# Sheet1.net
KiCad netlist of a schematic drawn in Altium Designer
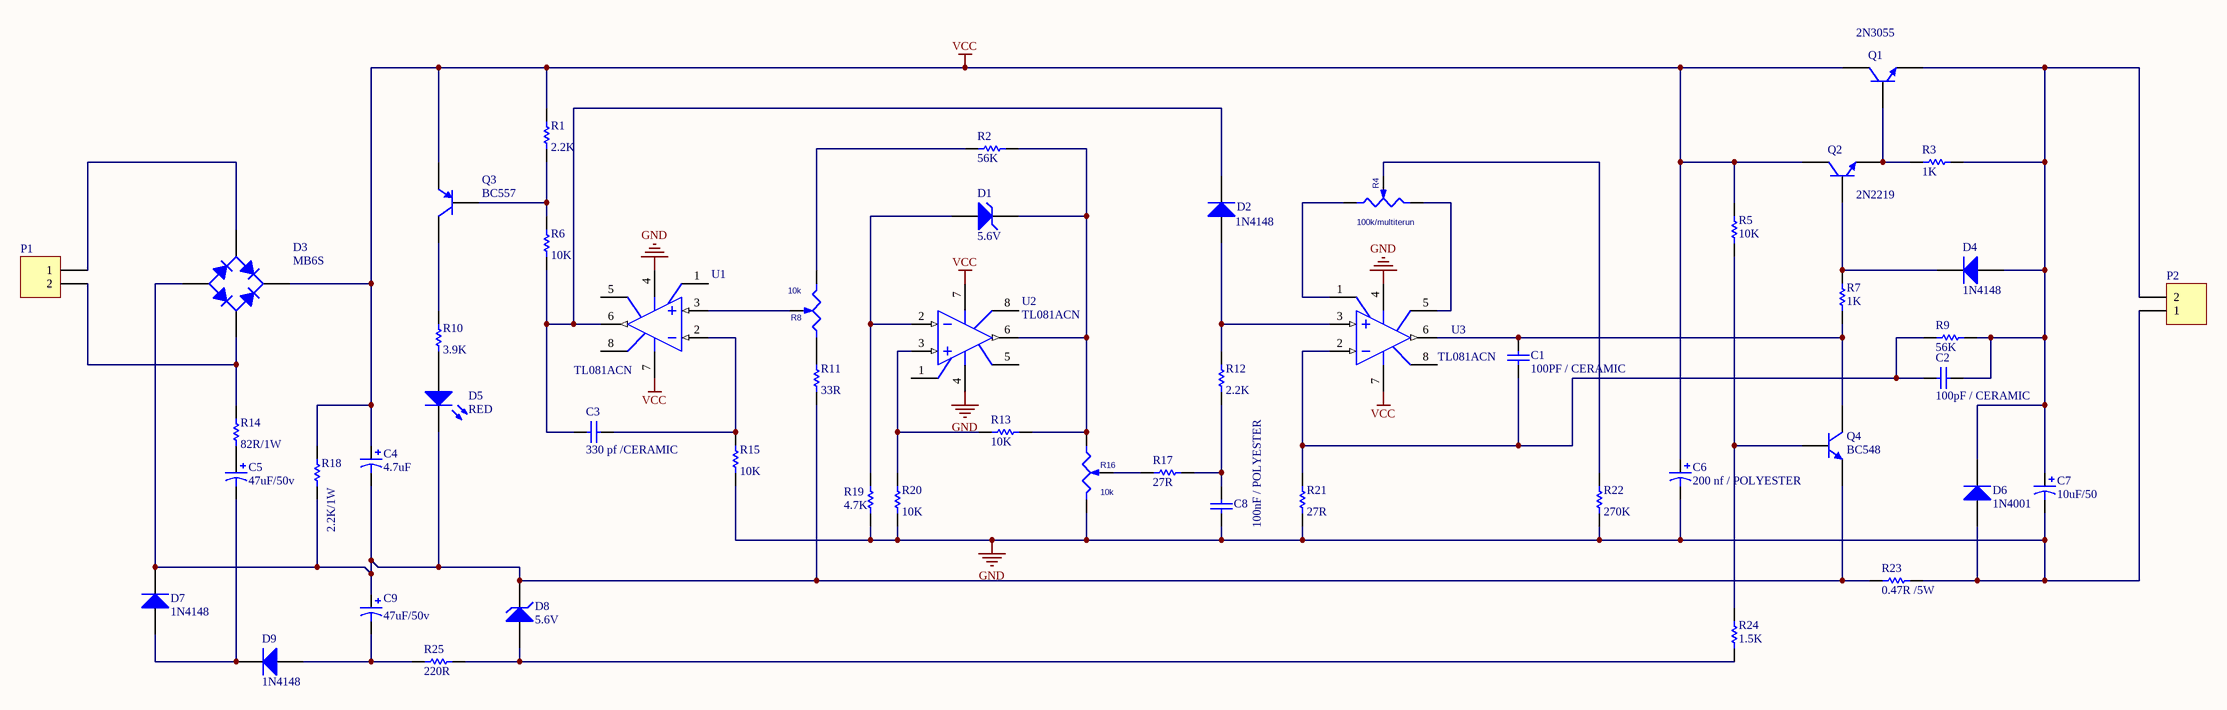
[diagram p0: Sheet1.SchDoc]

(export (version "E")
  (design (tool "Eeschema 10.0.6"))
  (components
    (comp (ref "C1")
      (value "100PF / CERAMIC")
      (footprint "RAD-0.1_cap")
      (description "Capacitor")
      (fields (field (name "PUBLISHER") "Altium Limited"))
      (libsource (lib "Miscellaneous Devices") (part "Cap"))
    )
    (comp (ref "C2")
      (value "100pF / CERAMIC")
      (footprint "RAD-0.1_cap")
      (description "Capacitor")
      (fields (field (name "PUBLISHER") "Altium Limited"))
      (libsource (lib "Miscellaneous Devices") (part "Cap"))
    )
    (comp (ref "C3")
      (value "330 pf /CERAMIC")
      (footprint "RAD-0.1_cap")
      (description "Capacitor")
      (fields (field (name "PUBLISHER") "Altium Limited"))
      (libsource (lib "Miscellaneous Devices") (part "Cap"))
    )
    (comp (ref "C4")
      (value "4.7uF")
      (footprint "Rad.1/.2-SMALL - duplicate")
      (description "Polarized Capacitor (Radial)")
      (fields (field (name "PUBLISHER") "Altium Limited"))
      (libsource (lib "Miscellaneous Devices") (part "Cap Pol1"))
    )
    (comp (ref "C5")
      (value "47uF/50v")
      (footprint "Rad.1/.2-SMALL - duplicate")
      (description "Polarized Capacitor (Radial)")
      (fields (field (name "PUBLISHER") "Altium Limited"))
      (libsource (lib "Miscellaneous Devices") (part "Cap Pol1"))
    )
    (comp (ref "C6")
      (value "200 nf / POLYESTER")
      (footprint "Rad.1/.2-SMALL - duplicate")
      (description "Polarized Capacitor (Radial)")
      (fields (field (name "PUBLISHER") "Altium Limited"))
      (libsource (lib "Miscellaneous Devices") (part "Cap Pol1"))
    )
    (comp (ref "C7")
      (value "10uF/50")
      (footprint "Rad.1/.2-SMALL - duplicate")
      (description "Polarized Capacitor (Radial)")
      (fields (field (name "PUBLISHER") "Altium Limited"))
      (libsource (lib "Miscellaneous Devices") (part "Cap Pol1"))
    )
    (comp (ref "C8")
      (value "100nF / POLYESTER")
      (footprint "RAD-0.2- duplicate")
      (description "Capacitor")
      (fields (field (name "PUBLISHER") "Altium Limited"))
      (libsource (lib "Miscellaneous Devices") (part "Cap"))
    )
    (comp (ref "C9")
      (value "47uF/50v")
      (footprint "Rad.1/.2-SMALL - duplicate")
      (description "Polarized Capacitor (Radial)")
      (fields (field (name "PUBLISHER") "Altium Limited"))
      (libsource (lib "Miscellaneous Devices") (part "Cap Pol1"))
    )
    (comp (ref "D1")
      (value "5.6V")
      (footprint "DIODE_ZENER.AXIAL0.3")
      (description "Zener Diode")
      (fields (field (name "PUBLISHER") "Altium Limited"))
      (libsource (lib "Miscellaneous Devices") (part "D Zener"))
    )
    (comp (ref "D2")
      (value "1N4148")
      (footprint "Dioad_1n400x_2")
      (description "1 Amp General Purpose Rectifier")
      (fields (field (name "PUBLISHER") "Altium Limited"))
      (libsource (lib "Miscellaneous Devices") (part "Diode 1N4007"))
    )
    (comp (ref "D3")
      (value "MB6S")
      (footprint "Bridge")
      (description "Full Wave Diode Bridge")
      (fields (field (name "PUBLISHER") "Altium Limited"))
      (libsource (lib "Miscellaneous Devices") (part "Bridge1"))
    )
    (comp (ref "D4")
      (value "1N4148")
      (footprint "Dioad_1n400x_2")
      (description "1 Amp General Purpose Rectifier")
      (fields (field (name "PUBLISHER") "Altium Limited"))
      (libsource (lib "Miscellaneous Devices") (part "Diode 1N4007"))
    )
    (comp (ref "D5")
      (value "RED")
      (footprint "Led_3mil - RED")
      (description "Typical INFRARED GaAs LED")
      (fields (field (name "PUBLISHER") "Altium Limited"))
      (libsource (lib "Miscellaneous Devices") (part "LED0"))
    )
    (comp (ref "D6")
      (value "1N4001")
      (footprint "Dioad_1n400x_2")
      (description "1 Amp General Purpose Rectifier")
      (fields (field (name "PUBLISHER") "Altium Limited"))
      (libsource (lib "Miscellaneous Devices") (part "Diode 1N4007"))
    )
    (comp (ref "D7")
      (value "1N4148")
      (footprint "Dioad_1n400x_2")
      (description "1 Amp General Purpose Rectifier")
      (fields (field (name "PUBLISHER") "Altium Limited"))
      (libsource (lib "Miscellaneous Devices") (part "Diode 1N4007"))
    )
    (comp (ref "D8")
      (value "5.6V")
      (footprint "DIODE_ZENER.AXIAL0.3")
      (description "Zener Diode")
      (fields (field (name "PUBLISHER") "Altium Limited"))
      (libsource (lib "Miscellaneous Devices") (part "D Zener"))
    )
    (comp (ref "D9")
      (value "1N4148")
      (footprint "Dioad_1n400x_2")
      (description "1 Amp General Purpose Rectifier")
      (fields (field (name "PUBLISHER") "Altium Limited"))
      (libsource (lib "Miscellaneous Devices") (part "Diode 1N4007"))
    )
    (comp (ref "P1")
      (value "24VDC/3A")
      (footprint "Blue Connector 1*2 -kf301")
      (description "Blue Connector 1*2 -kf301")
      (fields (field (name "PUBLISHER") "Altium Limited"))
      (libsource (lib "") (part "Header 2H_1"))
    )
    (comp (ref "P2")
      (value "Blue Connector 1*2 -kf301")
      (footprint "Blue Connector 1*2 -kf301")
      (fields (field (name "PUBLISHER") "Altium Limited"))
      (libsource (lib "Miscellaneous Connectors") (part "Header 2H"))
    )
    (comp (ref "Q1")
      (value "2N3055")
      (footprint "Blue Connector 1*3 -kf301")
      (description "NPN General Purpose Amplifier")
      (fields (field (name "PUBLISHER") "Altium Limited"))
      (libsource (lib "Miscellaneous Devices") (part "2N3904"))
    )
    (comp (ref "Q2")
      (value "2N2219")
      (footprint "TO-92A")
      (description "NPN General Purpose Amplifier")
      (fields (field (name "PUBLISHER") "Altium Limited"))
      (libsource (lib "Miscellaneous Devices") (part "2N3904"))
    )
    (comp (ref "Q3")
      (value "BC557")
      (footprint "TO-92A")
      (description "PNP General Purpose Amplifier")
      (fields (field (name "PUBLISHER") "Altium Limited"))
      (libsource (lib "Miscellaneous Devices") (part "2N3906"))
    )
    (comp (ref "Q4")
      (value "BC548")
      (footprint "TO-92A")
      (description "NPN General Purpose Amplifier")
      (fields (field (name "PUBLISHER") "Altium Limited"))
      (libsource (lib "Miscellaneous Devices") (part "2N3904"))
    )
    (comp (ref "R1")
      (value "2.2K")
      (footprint "AXIAL0.4 - 1k")
      (description "Resistor")
      (fields (field (name "PUBLISHER") "Altium Limited"))
      (libsource (lib "Miscellaneous Devices") (part "Res1"))
    )
    (comp (ref "R2")
      (value "56K")
      (footprint "AXIAL0.4 - 1k")
      (description "Resistor")
      (fields (field (name "PUBLISHER") "Altium Limited"))
      (libsource (lib "Miscellaneous Devices") (part "Res1"))
    )
    (comp (ref "R3")
      (value "1K")
      (footprint "AXIAL0.4 - 1k")
      (description "Resistor")
      (fields (field (name "PUBLISHER") "Altium Limited"))
      (libsource (lib "Miscellaneous Devices") (part "Res1"))
    )
    (comp (ref "R4") (value "100k/multiterun") (footprint "MULTITERN") (libsource (lib "*") (part "POT")))
    (comp (ref "R5")
      (value "10K")
      (footprint "AXIAL0.4 - 1k")
      (description "Resistor")
      (fields (field (name "PUBLISHER") "Altium Limited"))
      (libsource (lib "Miscellaneous Devices") (part "Res1"))
    )
    (comp (ref "R6")
      (value "10K")
      (footprint "AXIAL0.4 - 1k")
      (description "Resistor")
      (fields (field (name "PUBLISHER") "Altium Limited"))
      (libsource (lib "Miscellaneous Devices") (part "Res1"))
    )
    (comp (ref "R7")
      (value "1K")
      (footprint "AXIAL0.4 - 1k")
      (description "Resistor")
      (fields (field (name "PUBLISHER") "Altium Limited"))
      (libsource (lib "Miscellaneous Devices") (part "Res1"))
    )
    (comp (ref "R8") (value "10k") (footprint "Blue Connector 1*3 -kf301") (libsource (lib "*") (part "POT")))
    (comp (ref "R9")
      (value "56K")
      (footprint "AXIAL0.4 - 1k")
      (description "Resistor")
      (fields (field (name "PUBLISHER") "Altium Limited"))
      (libsource (lib "Miscellaneous Devices") (part "Res1"))
    )
    (comp (ref "R10")
      (value "3.9K")
      (footprint "AXIAL0.4 - 1k")
      (description "Resistor")
      (fields (field (name "PUBLISHER") "Altium Limited"))
      (libsource (lib "Miscellaneous Devices") (part "Res1"))
    )
    (comp (ref "R11")
      (value "33R")
      (footprint "AXIAL0.4 - 1k")
      (description "Resistor")
      (fields (field (name "PUBLISHER") "Altium Limited"))
      (libsource (lib "Miscellaneous Devices") (part "Res1"))
    )
    (comp (ref "R12")
      (value "2.2K")
      (footprint "AXIAL0.4 - 1k")
      (description "Resistor")
      (fields (field (name "PUBLISHER") "Altium Limited"))
      (libsource (lib "Miscellaneous Devices") (part "Res1"))
    )
    (comp (ref "R13")
      (value "10K")
      (footprint "AXIAL0.4 - 1k")
      (description "Resistor")
      (fields (field (name "PUBLISHER") "Altium Limited"))
      (libsource (lib "Miscellaneous Devices") (part "Res1"))
    )
    (comp (ref "R14")
      (value "82R/1W")
      (footprint "AXIAL0.4 - 1k")
      (description "Resistor")
      (fields (field (name "PUBLISHER") "Altium Limited"))
      (libsource (lib "Miscellaneous Devices") (part "Res1"))
    )
    (comp (ref "R15")
      (value "10K")
      (footprint "AXIAL0.4 - 1k")
      (description "Resistor")
      (fields (field (name "PUBLISHER") "Altium Limited"))
      (libsource (lib "Miscellaneous Devices") (part "Res1"))
    )
    (comp (ref "R16")
      (value "10k")
      (footprint "Blue Connector 1*3 -kf301")
      (libsource (lib "*") (part "POT"))
    )
    (comp (ref "R17")
      (value "27R")
      (footprint "AXIAL0.4 - 1k")
      (description "Resistor")
      (fields (field (name "PUBLISHER") "Altium Limited"))
      (libsource (lib "Miscellaneous Devices") (part "Res1"))
    )
    (comp (ref "R18")
      (value "2.2K/1W")
      (footprint "AXIAL0.4 - 1k")
      (description "Resistor")
      (fields (field (name "PUBLISHER") "Altium Limited"))
      (libsource (lib "Miscellaneous Devices") (part "Res1"))
    )
    (comp (ref "R19")
      (value "4.7K")
      (footprint "AXIAL0.4 - 1k")
      (description "Resistor")
      (fields (field (name "PUBLISHER") "Altium Limited"))
      (libsource (lib "Miscellaneous Devices") (part "Res1"))
    )
    (comp (ref "R20")
      (value "10K")
      (footprint "AXIAL0.4 - 1k")
      (description "Resistor")
      (fields (field (name "PUBLISHER") "Altium Limited"))
      (libsource (lib "Miscellaneous Devices") (part "Res1"))
    )
    (comp (ref "R21")
      (value "27R")
      (footprint "AXIAL0.4 - 1k")
      (description "Resistor")
      (fields (field (name "PUBLISHER") "Altium Limited"))
      (libsource (lib "Miscellaneous Devices") (part "Res1"))
    )
    (comp (ref "R22")
      (value "270K")
      (footprint "AXIAL0.4 - 1k")
      (description "Resistor")
      (fields (field (name "PUBLISHER") "Altium Limited"))
      (libsource (lib "Miscellaneous Devices") (part "Res1"))
    )
    (comp (ref "R23")
      (value "0.47R /5W")
      (footprint "AXIAL0.4 - 1k")
      (description "Resistor")
      (fields (field (name "PUBLISHER") "Altium Limited"))
      (libsource (lib "Miscellaneous Devices") (part "Res1"))
    )
    (comp (ref "R24")
      (value "1.5K")
      (footprint "AXIAL0.4 - 1k")
      (description "Resistor")
      (fields (field (name "PUBLISHER") "Altium Limited"))
      (libsource (lib "Miscellaneous Devices") (part "Res1"))
    )
    (comp (ref "R25")
      (value "220R")
      (footprint "AXIAL0.4 - 1k")
      (description "Resistor")
      (fields (field (name "PUBLISHER") "Altium Limited"))
      (libsource (lib "Miscellaneous Devices") (part "Res1"))
    )
    (comp (ref "U1")
      (value "TL081ACN")
      (footprint "DIP8")
      (description "General-Purpose J-FET Single Operational Amplifier")
      (fields (field (name "PUBLISHER") "Altium Limited"))
      (libsource (lib "ST Operational Amplifier") (part "TL081ACN"))
    )
    (comp (ref "U2")
      (value "TL081ACN")
      (footprint "DIP8")
      (description "General-Purpose J-FET Single Operational Amplifier")
      (fields (field (name "PUBLISHER") "Altium Limited"))
      (libsource (lib "ST Operational Amplifier") (part "TL081ACN"))
    )
    (comp (ref "U3")
      (value "TL081ACN")
      (footprint "DIP8")
      (description "General-Purpose J-FET Single Operational Amplifier")
      (fields (field (name "PUBLISHER") "Altium Limited"))
      (libsource (lib "ST Operational Amplifier") (part "TL081ACN"))
    )
  )
  (nets
    (net (code "1") (name "GND") (class "Default")
      (node (ref "C6") (pin "2") (pintype "passive"))
      (node (ref "C7") (pin "2") (pintype "passive"))
      (node (ref "C8") (pin "1") (pinfunction "1_1") (pintype "passive"))
      (node (ref "D6") (pin "1") (pinfunction "A_1") (pintype "passive"))
      (node (ref "P2") (pin "1") (pinfunction "1_1") (pintype "passive"))
      (node (ref "R15") (pin "1") (pinfunction "1_1") (pintype "passive"))
      (node (ref "R16") (pin "1") (pinfunction "A_1") (pintype "passive"))
      (node (ref "R19") (pin "2") (pinfunction "2_2") (pintype "passive"))
      (node (ref "R20") (pin "1") (pinfunction "1_1") (pintype "passive"))
      (node (ref "R21") (pin "1") (pinfunction "1_1") (pintype "passive"))
      (node (ref "R22") (pin "1") (pinfunction "1_1") (pintype "passive"))
      (node (ref "R23") (pin "1") (pinfunction "1_1") (pintype "passive"))
      (node (ref "U1") (pin "4") (pinfunction "V-_4") (pintype "power_in"))
      (node (ref "U2") (pin "4") (pinfunction "V-_4") (pintype "power_in"))
      (node (ref "U3") (pin "4") (pinfunction "V-_4") (pintype "power_in"))
    )
    (net (code "2") (name "Net-(C5-Pad1)") (class "Default")
      (node (ref "C5") (pin "1") (pintype "passive"))
      (node (ref "R14") (pin "1") (pinfunction "1_1") (pintype "passive"))
    )
    (net (code "3") (name "Net-(C8-Pad2)") (class "Default")
      (node (ref "C8") (pin "2") (pinfunction "2_2") (pintype "passive"))
      (node (ref "R12") (pin "1") (pinfunction "1_1") (pintype "passive"))
      (node (ref "R17") (pin "1") (pinfunction "1_1") (pintype "passive"))
    )
    (net (code "4") (name "Net-(D2-A)") (class "Default")
      (node (ref "D2") (pin "1") (pinfunction "A_1") (pintype "passive"))
      (node (ref "R12") (pin "2") (pinfunction "2_2") (pintype "passive"))
      (node (ref "U3") (pin "3") (pinfunction "IN+_3") (pintype "input"))
    )
    (net (code "5") (name "Net-(D2-K)") (class "Default")
      (node (ref "C3") (pin "2") (pinfunction "2_2") (pintype "passive"))
      (node (ref "D2") (pin "2") (pinfunction "K_2") (pintype "passive"))
      (node (ref "R6") (pin "1") (pinfunction "1_1") (pintype "passive"))
      (node (ref "U1") (pin "6") (pinfunction "OUT_6") (pintype "output"))
    )
    (net (code "6") (name "Net-(D3-A)") (class "Default")
      (node (ref "C4") (pin "2") (pintype "passive"))
      (node (ref "C9") (pin "1") (pintype "passive"))
      (node (ref "D3") (pin "3") (pinfunction "A_3") (pintype "passive"))
      (node (ref "D5") (pin "2") (pinfunction "K_2") (pintype "passive"))
      (node (ref "D7") (pin "2") (pinfunction "K_2") (pintype "passive"))
      (node (ref "D8") (pin "K") (pinfunction "K_K") (pintype "passive"))
      (node (ref "Q4") (pin "1") (pinfunction "E_1") (pintype "passive"))
      (node (ref "R11") (pin "1") (pinfunction "1_1") (pintype "passive"))
      (node (ref "R18") (pin "1") (pinfunction "1_1") (pintype "passive"))
      (node (ref "R23") (pin "2") (pinfunction "2_2") (pintype "passive"))
    )
    (net (code "7") (name "Net-(D3-C-Pad2)") (class "Default")
      (node (ref "D3") (pin "2") (pinfunction "C_2") (pintype "passive"))
      (node (ref "P1") (pin "2") (pinfunction "2_2") (pintype "passive"))
      (node (ref "R14") (pin "2") (pinfunction "2_2") (pintype "passive"))
    )
    (net (code "8") (name "Net-(D3-C-Pad4)") (class "Default")
      (node (ref "D3") (pin "4") (pinfunction "C_4") (pintype "passive"))
      (node (ref "P1") (pin "1") (pinfunction "1_1") (pintype "passive"))
    )
    (net (code "9") (name "Net-(D4-A)") (class "Default")
      (node (ref "C2") (pin "1") (pinfunction "1_1") (pintype "passive"))
      (node (ref "C7") (pin "1") (pintype "passive"))
      (node (ref "D4") (pin "1") (pinfunction "A_1") (pintype "passive"))
      (node (ref "D6") (pin "2") (pinfunction "K_2") (pintype "passive"))
      (node (ref "P2") (pin "2") (pinfunction "2_2") (pintype "passive"))
      (node (ref "Q1") (pin "1") (pinfunction "E_1") (pintype "passive"))
      (node (ref "R3") (pin "2") (pinfunction "2_2") (pintype "passive"))
      (node (ref "R9") (pin "2") (pinfunction "2_2") (pintype "passive"))
    )
    (net (code "10") (name "Net-(D4-K)") (class "Default")
      (node (ref "D4") (pin "2") (pinfunction "K_2") (pintype "passive"))
      (node (ref "Q2") (pin "2") (pinfunction "B_2") (pintype "passive"))
      (node (ref "R7") (pin "1") (pinfunction "1_1") (pintype "passive"))
    )
    (net (code "11") (name "Net-(D5-A)") (class "Default")
      (node (ref "D5") (pin "1") (pinfunction "A_1") (pintype "passive"))
      (node (ref "R10") (pin "1") (pinfunction "1_1") (pintype "passive"))
    )
    (net (code "12") (name "Net-(D7-A)") (class "Default")
      (node (ref "C5") (pin "2") (pintype "passive"))
      (node (ref "D7") (pin "1") (pinfunction "A_1") (pintype "passive"))
      (node (ref "D9") (pin "2") (pinfunction "K_2") (pintype "passive"))
    )
    (net (code "13") (name "Net-(D8-PadA)") (class "Default")
      (node (ref "D8") (pin "A") (pinfunction "A_A") (pintype "passive"))
      (node (ref "R24") (pin "2") (pinfunction "2_2") (pintype "passive"))
      (node (ref "R25") (pin "1") (pinfunction "1_1") (pintype "passive"))
    )
    (net (code "14") (name "Net-(D9-A)") (class "Default")
      (node (ref "C9") (pin "2") (pintype "passive"))
      (node (ref "D9") (pin "1") (pinfunction "A_1") (pintype "passive"))
      (node (ref "R25") (pin "2") (pinfunction "2_2") (pintype "passive"))
    )
    (net (code "15") (name "Net-(Q1-B)") (class "Default")
      (node (ref "Q1") (pin "2") (pinfunction "B_2") (pintype "passive"))
      (node (ref "Q2") (pin "1") (pinfunction "E_1") (pintype "passive"))
      (node (ref "R3") (pin "1") (pinfunction "1_1") (pintype "passive"))
    )
    (net (code "16") (name "Net-(Q3-B)") (class "Default")
      (node (ref "Q3") (pin "2") (pinfunction "B_2") (pintype "passive"))
      (node (ref "R1") (pin "1") (pinfunction "1_1") (pintype "passive"))
      (node (ref "R6") (pin "2") (pinfunction "2_2") (pintype "passive"))
    )
    (net (code "17") (name "Net-(Q3-C)") (class "Default")
      (node (ref "Q3") (pin "3") (pinfunction "C_3") (pintype "passive"))
      (node (ref "R10") (pin "2") (pinfunction "2_2") (pintype "passive"))
    )
    (net (code "18") (name "Net-(Q4-B)") (class "Default")
      (node (ref "Q4") (pin "2") (pinfunction "B_2") (pintype "passive"))
      (node (ref "R24") (pin "1") (pinfunction "1_1") (pintype "passive"))
      (node (ref "R5") (pin "2") (pinfunction "2_2") (pintype "passive"))
    )
    (net (code "19") (name "Net-(Q4-C)") (class "Default")
      (node (ref "C1") (pin "2") (pinfunction "2_2") (pintype "passive"))
      (node (ref "Q4") (pin "3") (pinfunction "C_3") (pintype "passive"))
      (node (ref "R7") (pin "2") (pinfunction "2_2") (pintype "passive"))
      (node (ref "U3") (pin "6") (pinfunction "OUT_6") (pintype "output"))
    )
    (net (code "20") (name "Net-(R4-A)") (class "Default")
      (node (ref "R4") (pin "1") (pinfunction "A_1") (pintype "passive"))
      (node (ref "U3") (pin "5") (pinfunction "OS_NULL_5") (pintype "passive"))
    )
    (net (code "21") (name "Net-(R4-B)") (class "Default")
      (node (ref "R4") (pin "3") (pinfunction "B_3") (pintype "passive"))
      (node (ref "U3") (pin "1") (pinfunction "OS_NULL_1") (pintype "passive"))
    )
    (net (code "22") (name "Net-(R4-WIPER)") (class "Default")
      (node (ref "R22") (pin "2") (pinfunction "2_2") (pintype "passive"))
      (node (ref "R4") (pin "2") (pinfunction "WIPER_2") (pintype "passive"))
    )
    (net (code "23") (name "Net-(R8-A)") (class "Default")
      (node (ref "R2") (pin "2") (pinfunction "2_2") (pintype "passive"))
      (node (ref "R8") (pin "1") (pinfunction "A_1") (pintype "passive"))
    )
    (net (code "24") (name "Net-(R8-B)") (class "Default")
      (node (ref "R11") (pin "2") (pinfunction "2_2") (pintype "passive"))
      (node (ref "R8") (pin "3") (pinfunction "B_3") (pintype "passive"))
    )
    (net (code "25") (name "Net-(R8-WIPER)") (class "Default")
      (node (ref "R8") (pin "2") (pinfunction "WIPER_2") (pintype "passive"))
      (node (ref "U1") (pin "3") (pinfunction "IN+_3") (pintype "input"))
    )
    (net (code "26") (name "Net-(R16-B)") (class "Default")
      (node (ref "D1") (pin "K") (pinfunction "K_K") (pintype "passive"))
      (node (ref "R13") (pin "1") (pinfunction "1_1") (pintype "passive"))
      (node (ref "R16") (pin "3") (pinfunction "B_3") (pintype "passive"))
      (node (ref "R2") (pin "1") (pinfunction "1_1") (pintype "passive"))
      (node (ref "U2") (pin "6") (pinfunction "OUT_6") (pintype "output"))
    )
    (net (code "27") (name "Net-(R16-WIPER)") (class "Default")
      (node (ref "R16") (pin "2") (pinfunction "WIPER_2") (pintype "passive"))
      (node (ref "R17") (pin "2") (pinfunction "2_2") (pintype "passive"))
    )
    (net (code "28") (name "Net-(U1-IN-)") (class "Default")
      (node (ref "C3") (pin "1") (pinfunction "1_1") (pintype "passive"))
      (node (ref "R15") (pin "2") (pinfunction "2_2") (pintype "passive"))
      (node (ref "U1") (pin "2") (pinfunction "IN-_2") (pintype "input"))
    )
    (net (code "29") (name "Net-(U2-IN+)") (class "Default")
      (node (ref "R13") (pin "2") (pinfunction "2_2") (pintype "passive"))
      (node (ref "R20") (pin "2") (pinfunction "2_2") (pintype "passive"))
      (node (ref "U2") (pin "3") (pinfunction "IN+_3") (pintype "input"))
    )
    (net (code "30") (name "Net-(U2-IN-)") (class "Default")
      (node (ref "D1") (pin "A") (pinfunction "A_A") (pintype "passive"))
      (node (ref "R19") (pin "1") (pinfunction "1_1") (pintype "passive"))
      (node (ref "U2") (pin "2") (pinfunction "IN-_2") (pintype "input"))
    )
    (net (code "31") (name "Net-(U3-IN-)") (class "Default")
      (node (ref "C1") (pin "1") (pinfunction "1_1") (pintype "passive"))
      (node (ref "C2") (pin "2") (pinfunction "2_2") (pintype "passive"))
      (node (ref "R21") (pin "2") (pinfunction "2_2") (pintype "passive"))
      (node (ref "R9") (pin "1") (pinfunction "1_1") (pintype "passive"))
      (node (ref "U3") (pin "2") (pinfunction "IN-_2") (pintype "input"))
    )
    (net (code "32") (name "VCC") (class "Default")
      (node (ref "C4") (pin "1") (pintype "passive"))
      (node (ref "C6") (pin "1") (pintype "passive"))
      (node (ref "D3") (pin "1") (pinfunction "K_1") (pintype "passive"))
      (node (ref "Q1") (pin "3") (pinfunction "C_3") (pintype "passive"))
      (node (ref "Q2") (pin "3") (pinfunction "C_3") (pintype "passive"))
      (node (ref "Q3") (pin "1") (pinfunction "E_1") (pintype "passive"))
      (node (ref "R1") (pin "2") (pinfunction "2_2") (pintype "passive"))
      (node (ref "R18") (pin "2") (pinfunction "2_2") (pintype "passive"))
      (node (ref "R5") (pin "1") (pinfunction "1_1") (pintype "passive"))
      (node (ref "U1") (pin "7") (pinfunction "V+_7") (pintype "power_in"))
      (node (ref "U2") (pin "7") (pinfunction "V+_7") (pintype "power_in"))
      (node (ref "U3") (pin "7") (pinfunction "V+_7") (pintype "power_in"))
    )
    (net (code "33") (name "unconnected-(U1-NC-Pad8)") (class "Default")
      (node (ref "U1") (pin "8") (pinfunction "NC_8") (pintype "passive"))
    )
    (net (code "34") (name "unconnected-(U1-OS_NULL-Pad1)") (class "Default")
      (node (ref "U1") (pin "1") (pinfunction "OS_NULL_1") (pintype "passive"))
    )
    (net (code "35") (name "unconnected-(U1-OS_NULL-Pad5)") (class "Default")
      (node (ref "U1") (pin "5") (pinfunction "OS_NULL_5") (pintype "passive"))
    )
    (net (code "36") (name "unconnected-(U2-NC-Pad8)") (class "Default")
      (node (ref "U2") (pin "8") (pinfunction "NC_8") (pintype "passive"))
    )
    (net (code "37") (name "unconnected-(U2-OS_NULL-Pad1)") (class "Default")
      (node (ref "U2") (pin "1") (pinfunction "OS_NULL_1") (pintype "passive"))
    )
    (net (code "38") (name "unconnected-(U2-OS_NULL-Pad5)") (class "Default")
      (node (ref "U2") (pin "5") (pinfunction "OS_NULL_5") (pintype "passive"))
    )
    (net (code "39") (name "unconnected-(U3-NC-Pad8)") (class "Default")
      (node (ref "U3") (pin "8") (pinfunction "NC_8") (pintype "passive"))
    )
  )
)
